# Frequency_synthesizer_v1_0.net
KiCad netlist of a schematic drawn in EAGLE
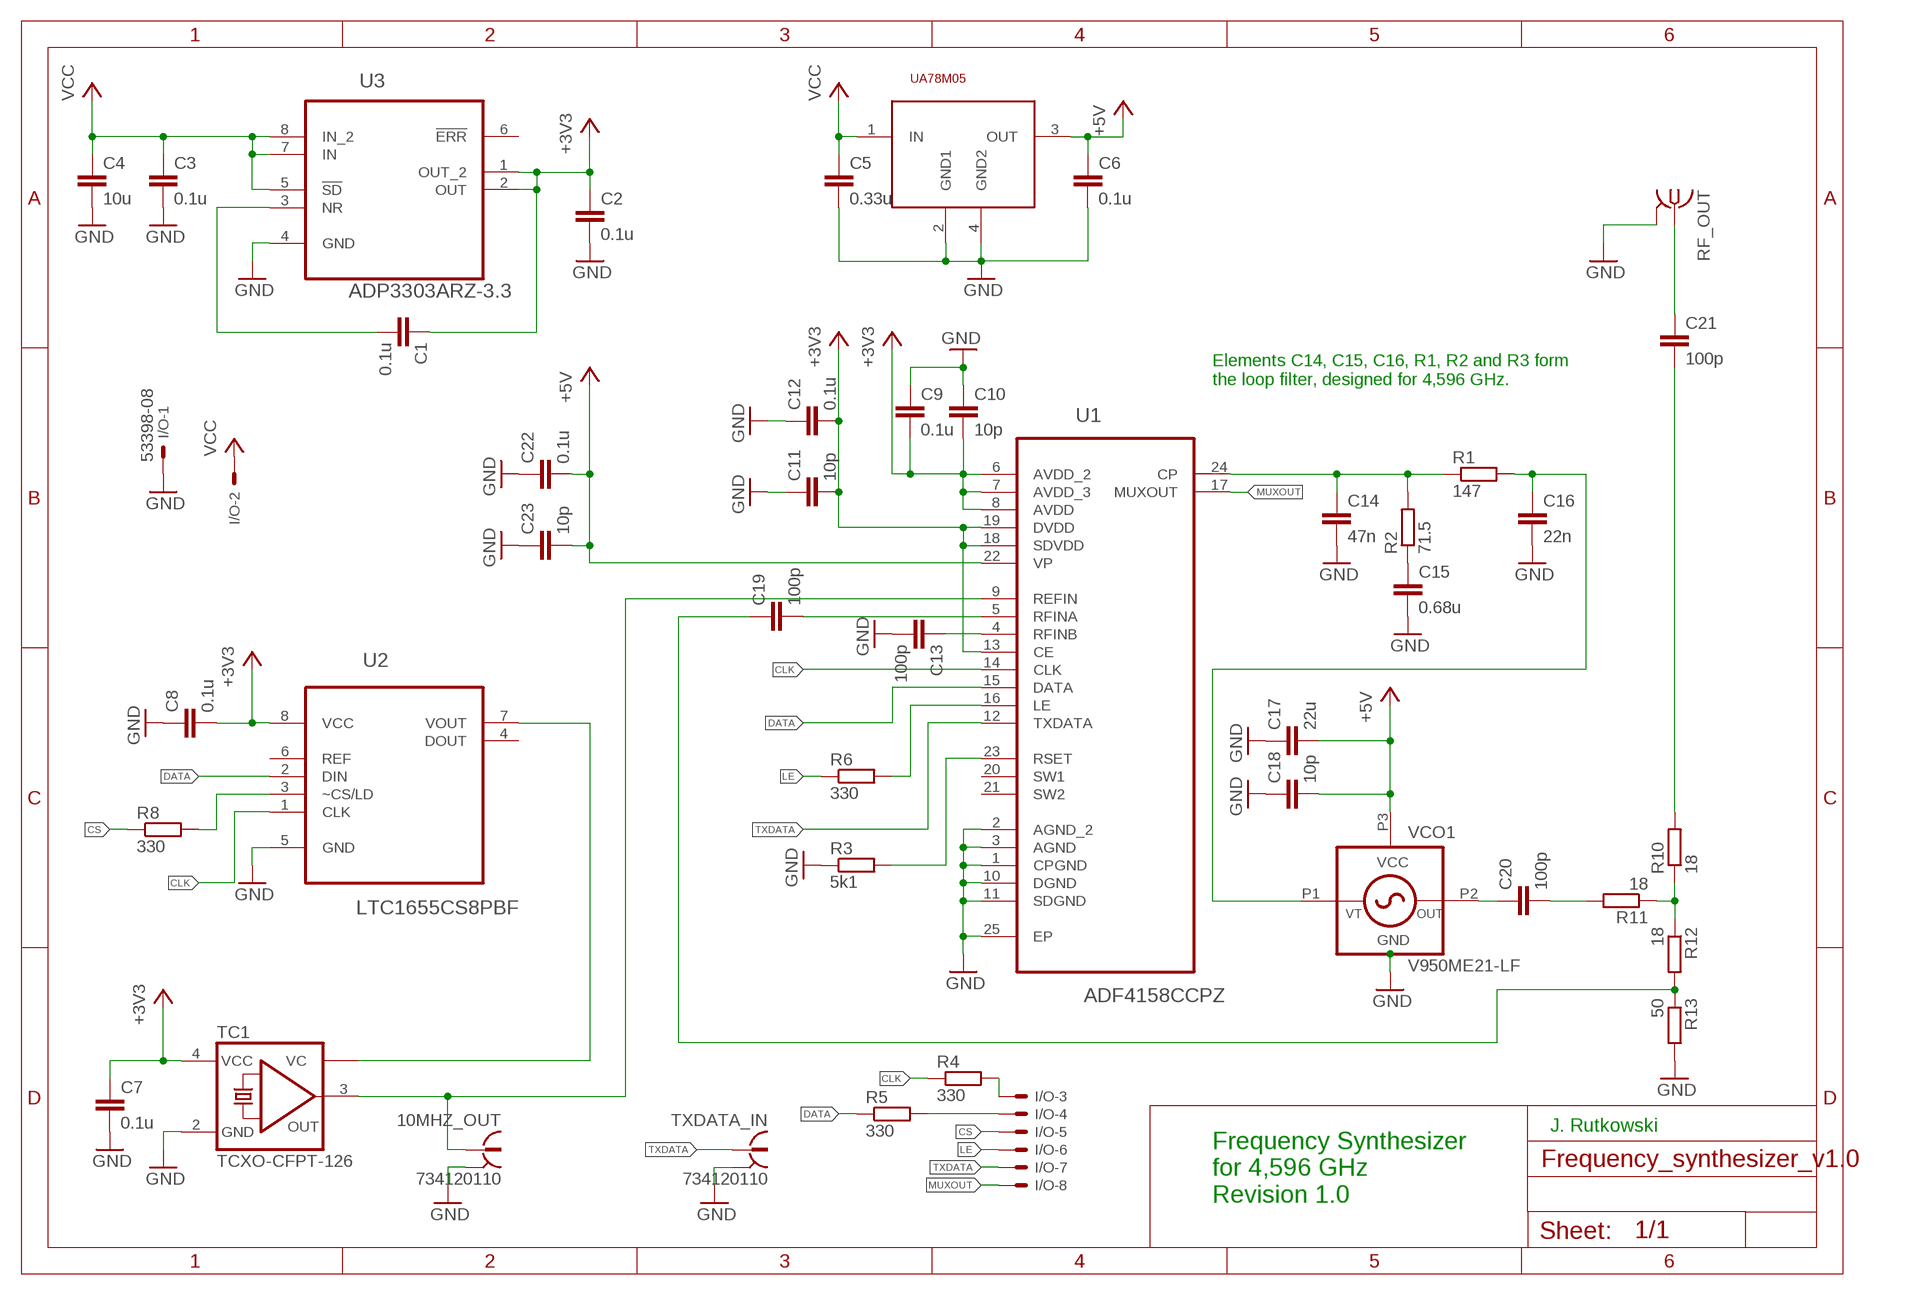
[diagram p0: schematic, sheet 1]

(export (version "E")
  (design (tool "Eeschema 10.0.6"))
  (components
    (comp (ref "10MHZ_OUT")
      (value "734120110")
      (footprint "eagle-import:734120110")
      (libsource (lib "eagle-import") (part "734120110"))
    )
    (comp (ref "C1")
      (value "0.1u")
      (footprint "eagle-import:C0603K")
      (libsource (lib "eagle-import") (part "C-EUC0603K"))
    )
    (comp (ref "C2")
      (value "0.1u")
      (footprint "eagle-import:C0603K")
      (libsource (lib "eagle-import") (part "C-EUC0603K"))
    )
    (comp (ref "C3")
      (value "0.1u")
      (footprint "eagle-import:C0603K")
      (libsource (lib "eagle-import") (part "C-EUC0603K"))
    )
    (comp (ref "C4")
      (value "10u")
      (footprint "eagle-import:C0805K")
      (libsource (lib "eagle-import") (part "C-EUC0805K"))
    )
    (comp (ref "C5")
      (value "0.33u")
      (footprint "eagle-import:C0603K")
      (libsource (lib "eagle-import") (part "C-EUC0603K"))
    )
    (comp (ref "C6")
      (value "0.1u")
      (footprint "eagle-import:C0603K")
      (libsource (lib "eagle-import") (part "C-EUC0603K"))
    )
    (comp (ref "C7")
      (value "0.1u")
      (footprint "eagle-import:C0603K")
      (libsource (lib "eagle-import") (part "C-EUC0603K"))
    )
    (comp (ref "C8")
      (value "0.1u")
      (footprint "eagle-import:C0603K")
      (libsource (lib "eagle-import") (part "C-EUC0603K"))
    )
    (comp (ref "C9")
      (value "0.1u")
      (footprint "eagle-import:C0603K")
      (libsource (lib "eagle-import") (part "C-EUC0603K"))
    )
    (comp (ref "C10")
      (value "10p")
      (footprint "eagle-import:C0603K")
      (libsource (lib "eagle-import") (part "C-EUC0603K"))
    )
    (comp (ref "C11")
      (value "10p")
      (footprint "eagle-import:C0603K")
      (libsource (lib "eagle-import") (part "C-EUC0603K"))
    )
    (comp (ref "C12")
      (value "0.1u")
      (footprint "eagle-import:C0603K")
      (libsource (lib "eagle-import") (part "C-EUC0603K"))
    )
    (comp (ref "C13")
      (value "100p")
      (footprint "eagle-import:C0402")
      (libsource (lib "eagle-import") (part "C-EUC0402"))
    )
    (comp (ref "C14")
      (value "47n")
      (footprint "eagle-import:C0603K")
      (libsource (lib "eagle-import") (part "C-EUC0603K"))
    )
    (comp (ref "C15")
      (value "0.68u")
      (footprint "eagle-import:C0603K")
      (libsource (lib "eagle-import") (part "C-EUC0603K"))
    )
    (comp (ref "C16")
      (value "22n")
      (footprint "eagle-import:C0603K")
      (libsource (lib "eagle-import") (part "C-EUC0603K"))
    )
    (comp (ref "C17")
      (value "22u")
      (footprint "eagle-import:C0805")
      (libsource (lib "eagle-import") (part "C-EUC0805"))
    )
    (comp (ref "C18")
      (value "10p")
      (footprint "eagle-import:C0603K")
      (libsource (lib "eagle-import") (part "C-EUC0603K"))
    )
    (comp (ref "C19")
      (value "100p")
      (footprint "eagle-import:C0402")
      (libsource (lib "eagle-import") (part "C-EUC0402"))
    )
    (comp (ref "C20")
      (value "100p")
      (footprint "eagle-import:C0402")
      (libsource (lib "eagle-import") (part "C-EUC0402"))
    )
    (comp (ref "C21")
      (value "100p")
      (footprint "eagle-import:C0402")
      (libsource (lib "eagle-import") (part "C-EUC0402"))
    )
    (comp (ref "C22")
      (value "0.1u")
      (footprint "eagle-import:C0603K")
      (libsource (lib "eagle-import") (part "C-EUC0603K"))
    )
    (comp (ref "C23")
      (value "10p")
      (footprint "eagle-import:C0603K")
      (libsource (lib "eagle-import") (part "C-EUC0603K"))
    )
    (comp (ref "I/O")
      (value "53398-08")
      (footprint "eagle-import:53398-08")
      (libsource (lib "eagle-import") (part "53?-08398"))
    )
    (comp (ref "R1")
      (value "147")
      (footprint "eagle-import:R0603")
      (libsource (lib "eagle-import") (part "R-EU_R0603"))
    )
    (comp (ref "R2")
      (value "71.5")
      (footprint "eagle-import:R0603")
      (libsource (lib "eagle-import") (part "R-EU_R0603"))
    )
    (comp (ref "R3")
      (value "5k1")
      (footprint "eagle-import:R0603")
      (libsource (lib "eagle-import") (part "R-EU_R0603"))
    )
    (comp (ref "R4")
      (value "330")
      (footprint "eagle-import:R0603")
      (libsource (lib "eagle-import") (part "R-EU_R0603"))
    )
    (comp (ref "R5")
      (value "330")
      (footprint "eagle-import:R0603")
      (libsource (lib "eagle-import") (part "R-EU_R0603"))
    )
    (comp (ref "R6")
      (value "330")
      (footprint "eagle-import:R0603")
      (libsource (lib "eagle-import") (part "R-EU_R0603"))
    )
    (comp (ref "R8")
      (value "330")
      (footprint "eagle-import:R0603")
      (libsource (lib "eagle-import") (part "R-EU_R0603"))
    )
    (comp (ref "R10")
      (value "18")
      (footprint "eagle-import:R0402")
      (libsource (lib "eagle-import") (part "R-EU_R0402"))
    )
    (comp (ref "R11")
      (value "18")
      (footprint "eagle-import:R0402")
      (libsource (lib "eagle-import") (part "R-EU_R0402"))
    )
    (comp (ref "R12")
      (value "18")
      (footprint "eagle-import:R0402")
      (libsource (lib "eagle-import") (part "R-EU_R0402"))
    )
    (comp (ref "R13")
      (value "50")
      (footprint "eagle-import:R0402")
      (libsource (lib "eagle-import") (part "R-EU_R0402"))
    )
    (comp (ref "RF_OUT")
      (value "SMA-142-0711-871/876")
      (footprint "eagle-import:J502-ND-142-0711-871_876")
      (fields (field (name "MF") "JOHNSON COMPONENTS") (field (name "MPN") "142-0711-871"))
      (libsource (lib "eagle-import") (part "SMA-142-0711-871/876"))
    )
    (comp (ref "TC1")
      (value "TCXO-CFPT-126")
      (footprint "eagle-import:7.0X5.0-4-PAD")
      (libsource (lib "eagle-import") (part "TCXO-CFPT-126"))
    )
    (comp (ref "TXDATA_IN")
      (value "734120110")
      (footprint "eagle-import:734120110")
      (libsource (lib "eagle-import") (part "734120110"))
    )
    (comp (ref "U$1")
      (value "UA78M05")
      (footprint "eagle-import:SOT-223")
      (libsource (lib "eagle-import") (part "UA78M05"))
    )
    (comp (ref "U1")
      (value "ADF4158CCPZ")
      (footprint "eagle-import:QFN50P400X400X80-25N")
      (libsource (lib "eagle-import") (part "ADF4158CCPZ"))
    )
    (comp (ref "U2")
      (value "LTC1655CS8PBF")
      (footprint "eagle-import:SOIC127P600X175-8N")
      (fields (field (name "MPN") "LTC1655CS8#PBF"))
      (libsource (lib "eagle-import") (part "LTC1655CS8PBF"))
    )
    (comp (ref "U3")
      (value "ADP3303ARZ-3.3")
      (footprint "eagle-import:SOIC127P600X175-8N")
      (libsource (lib "eagle-import") (part "ADP3303ARZ-3.3"))
    )
    (comp (ref "VCO1")
      (value "V950ME21-LF")
      (footprint "eagle-import:MINI-14S")
      (libsource (lib "eagle-import") (part "MINI-14S"))
    )
  )
  (nets
    (net (code "1") (name "+3V3") (class "Default")
      (node (ref "C1") (pin "1") (pinfunction "1_1") (pintype "passive"))
      (node (ref "C10") (pin "2") (pinfunction "2_2") (pintype "passive"))
      (node (ref "C11") (pin "2") (pinfunction "2_2") (pintype "passive"))
      (node (ref "C12") (pin "2") (pinfunction "2_2") (pintype "passive"))
      (node (ref "C2") (pin "1") (pinfunction "1_1") (pintype "passive"))
      (node (ref "C7") (pin "1") (pinfunction "1_1") (pintype "passive"))
      (node (ref "C8") (pin "2") (pinfunction "2_2") (pintype "passive"))
      (node (ref "C9") (pin "2") (pinfunction "2_2") (pintype "passive"))
      (node (ref "TC1") (pin "4") (pinfunction "VCC_4") (pintype "power_in"))
      (node (ref "U1") (pin "13") (pinfunction "CE_13") (pintype "input"))
      (node (ref "U1") (pin "18") (pinfunction "SDVDD_18") (pintype "power_in"))
      (node (ref "U1") (pin "19") (pinfunction "DVDD_19") (pintype "power_in"))
      (node (ref "U1") (pin "6") (pinfunction "AVDD_2_6") (pintype "power_in"))
      (node (ref "U1") (pin "7") (pinfunction "AVDD_3_7") (pintype "power_in"))
      (node (ref "U1") (pin "8") (pinfunction "AVDD_8") (pintype "power_in"))
      (node (ref "U2") (pin "8") (pinfunction "VCC_8") (pintype "power_in"))
      (node (ref "U3") (pin "1") (pinfunction "OUT_2_1") (pintype "output"))
      (node (ref "U3") (pin "2") (pinfunction "OUT_2") (pintype "output"))
    )
    (net (code "2") (name "+5V") (class "Default")
      (node (ref "C17") (pin "2") (pinfunction "2_2") (pintype "passive"))
      (node (ref "C18") (pin "2") (pinfunction "2_2") (pintype "passive"))
      (node (ref "C22") (pin "2") (pinfunction "2_2") (pintype "passive"))
      (node (ref "C23") (pin "2") (pinfunction "2_2") (pintype "passive"))
      (node (ref "C6") (pin "1") (pinfunction "1_1") (pintype "passive"))
      (node (ref "U$1") (pin "3") (pinfunction "OUT_3") (pintype "bidirectional"))
      (node (ref "U1") (pin "22") (pinfunction "VP_22") (pintype "power_in"))
      (node (ref "VCO1") (pin "P3") (pinfunction "VCC_P3") (pintype "power_in"))
    )
    (net (code "3") (name "CLK") (class "Default")
      (node (ref "R4") (pin "1") (pinfunction "1_1") (pintype "passive"))
      (node (ref "U1") (pin "14") (pinfunction "CLK_14") (pintype "input"))
      (node (ref "U2") (pin "1") (pinfunction "CLK_1") (pintype "input"))
    )
    (net (code "4") (name "CS") (class "Default")
      (node (ref "I/O") (pin "5") (pinfunction "S_5") (pintype "passive"))
      (node (ref "R8") (pin "1") (pinfunction "1_1") (pintype "passive"))
    )
    (net (code "5") (name "DATA") (class "Default")
      (node (ref "R5") (pin "1") (pinfunction "1_1") (pintype "passive"))
      (node (ref "U1") (pin "15") (pinfunction "DATA_15") (pintype "input"))
      (node (ref "U2") (pin "2") (pinfunction "DIN_2") (pintype "input"))
    )
    (net (code "6") (name "GND") (class "Default")
      (node (ref "10MHZ_OUT") (pin "S@1") (pinfunction "2_S@1") (pintype "passive"))
      (node (ref "10MHZ_OUT") (pin "S@2") (pinfunction "2_S@2") (pintype "passive"))
      (node (ref "10MHZ_OUT") (pin "S@3") (pinfunction "2_S@3") (pintype "passive"))
      (node (ref "C10") (pin "1") (pinfunction "1_1") (pintype "passive"))
      (node (ref "C11") (pin "1") (pinfunction "1_1") (pintype "passive"))
      (node (ref "C12") (pin "1") (pinfunction "1_1") (pintype "passive"))
      (node (ref "C13") (pin "2") (pinfunction "2_2") (pintype "passive"))
      (node (ref "C14") (pin "2") (pinfunction "2_2") (pintype "passive"))
      (node (ref "C15") (pin "2") (pinfunction "2_2") (pintype "passive"))
      (node (ref "C16") (pin "2") (pinfunction "2_2") (pintype "passive"))
      (node (ref "C17") (pin "1") (pinfunction "1_1") (pintype "passive"))
      (node (ref "C18") (pin "1") (pinfunction "1_1") (pintype "passive"))
      (node (ref "C2") (pin "2") (pinfunction "2_2") (pintype "passive"))
      (node (ref "C22") (pin "1") (pinfunction "1_1") (pintype "passive"))
      (node (ref "C23") (pin "1") (pinfunction "1_1") (pintype "passive"))
      (node (ref "C3") (pin "2") (pinfunction "2_2") (pintype "passive"))
      (node (ref "C4") (pin "2") (pinfunction "2_2") (pintype "passive"))
      (node (ref "C5") (pin "2") (pinfunction "2_2") (pintype "passive"))
      (node (ref "C6") (pin "2") (pinfunction "2_2") (pintype "passive"))
      (node (ref "C7") (pin "2") (pinfunction "2_2") (pintype "passive"))
      (node (ref "C8") (pin "1") (pinfunction "1_1") (pintype "passive"))
      (node (ref "C9") (pin "1") (pinfunction "1_1") (pintype "passive"))
      (node (ref "I/O") (pin "1") (pinfunction "S_1") (pintype "passive"))
      (node (ref "R13") (pin "2") (pinfunction "2_2") (pintype "passive"))
      (node (ref "R3") (pin "1") (pinfunction "1_1") (pintype "passive"))
      (node (ref "RF_OUT") (pin "G@1") (pinfunction "2_G@1") (pintype "passive"))
      (node (ref "RF_OUT") (pin "G@2") (pinfunction "2_G@2") (pintype "passive"))
      (node (ref "RF_OUT") (pin "G@3") (pinfunction "2_G@3") (pintype "passive"))
      (node (ref "RF_OUT") (pin "G@4") (pinfunction "2_G@4") (pintype "passive"))
      (node (ref "TC1") (pin "2") (pinfunction "GND_2") (pintype "power_in"))
      (node (ref "TXDATA_IN") (pin "S@1") (pinfunction "2_S@1") (pintype "passive"))
      (node (ref "TXDATA_IN") (pin "S@2") (pinfunction "2_S@2") (pintype "passive"))
      (node (ref "TXDATA_IN") (pin "S@3") (pinfunction "2_S@3") (pintype "passive"))
      (node (ref "U$1") (pin "2") (pinfunction "GND1_2") (pintype "bidirectional"))
      (node (ref "U$1") (pin "4") (pinfunction "GND2_4") (pintype "bidirectional"))
      (node (ref "U1") (pin "1") (pinfunction "CPGND_1") (pintype "passive"))
      (node (ref "U1") (pin "10") (pinfunction "DGND_10") (pintype "passive"))
      (node (ref "U1") (pin "11") (pinfunction "SDGND_11") (pintype "passive"))
      (node (ref "U1") (pin "2") (pinfunction "AGND_2_2") (pintype "passive"))
      (node (ref "U1") (pin "25") (pinfunction "EP_25") (pintype "passive"))
      (node (ref "U1") (pin "3") (pinfunction "AGND_3") (pintype "passive"))
      (node (ref "U2") (pin "5") (pinfunction "GND_5") (pintype "passive"))
      (node (ref "U3") (pin "4") (pinfunction "GND_4") (pintype "passive"))
      (node (ref "VCO1") (pin "S1") (pinfunction "S1_S1") (pintype "power_in"))
      (node (ref "VCO1") (pin "S10") (pinfunction "S10_S10") (pintype "power_in"))
      (node (ref "VCO1") (pin "S11") (pinfunction "S11_S11") (pintype "power_in"))
      (node (ref "VCO1") (pin "S2") (pinfunction "S2_S2") (pintype "power_in"))
      (node (ref "VCO1") (pin "S3") (pinfunction "S3_S3") (pintype "power_in"))
      (node (ref "VCO1") (pin "S4") (pinfunction "S4_S4") (pintype "power_in"))
      (node (ref "VCO1") (pin "S5") (pinfunction "S5_S5") (pintype "power_in"))
      (node (ref "VCO1") (pin "S6") (pinfunction "S6_S6") (pintype "power_in"))
      (node (ref "VCO1") (pin "S7") (pinfunction "S7_S7") (pintype "power_in"))
      (node (ref "VCO1") (pin "S8") (pinfunction "S8_S8") (pintype "power_in"))
      (node (ref "VCO1") (pin "S9") (pinfunction "S9_S9") (pintype "power_in"))
    )
    (net (code "7") (name "LE") (class "Default")
      (node (ref "I/O") (pin "6") (pinfunction "S_6") (pintype "passive"))
      (node (ref "R6") (pin "1") (pinfunction "1_1") (pintype "passive"))
    )
    (net (code "8") (name "MUXOUT") (class "Default")
      (node (ref "I/O") (pin "8") (pinfunction "S_8") (pintype "passive"))
      (node (ref "U1") (pin "17") (pinfunction "MUXOUT_17") (pintype "output"))
    )
    (net (code "9") (name "Net-(C15-Pad1)") (class "Default")
      (node (ref "C15") (pin "1") (pinfunction "1_1") (pintype "passive"))
      (node (ref "R2") (pin "1") (pinfunction "1_1") (pintype "passive"))
    )
    (net (code "10") (name "Net-(C19-Pad1)") (class "Default")
      (node (ref "C19") (pin "1") (pinfunction "1_1") (pintype "passive"))
      (node (ref "R12") (pin "2") (pinfunction "2_2") (pintype "passive"))
      (node (ref "R13") (pin "1") (pinfunction "1_1") (pintype "passive"))
    )
    (net (code "11") (name "Net-(C20-Pad2)") (class "Default")
      (node (ref "C20") (pin "2") (pinfunction "2_2") (pintype "passive"))
      (node (ref "R11") (pin "2") (pinfunction "2_2") (pintype "passive"))
    )
    (net (code "12") (name "Net-(C21-Pad1)") (class "Default")
      (node (ref "C21") (pin "1") (pinfunction "1_1") (pintype "passive"))
      (node (ref "RF_OUT") (pin "1") (pinfunction "1_1") (pintype "passive"))
    )
    (net (code "13") (name "Net-(C21-Pad2)") (class "Default")
      (node (ref "C21") (pin "2") (pinfunction "2_2") (pintype "passive"))
      (node (ref "R10") (pin "2") (pinfunction "2_2") (pintype "passive"))
    )
    (net (code "14") (name "Net-(I/OC-S)") (class "Default")
      (node (ref "I/O") (pin "3") (pinfunction "S_3") (pintype "passive"))
      (node (ref "R4") (pin "2") (pinfunction "2_2") (pintype "passive"))
    )
    (net (code "15") (name "Net-(I/OD-S)") (class "Default")
      (node (ref "I/O") (pin "4") (pinfunction "S_4") (pintype "passive"))
      (node (ref "R5") (pin "2") (pinfunction "2_2") (pintype "passive"))
    )
    (net (code "16") (name "Net-(R10-Pad1)") (class "Default")
      (node (ref "R10") (pin "1") (pinfunction "1_1") (pintype "passive"))
      (node (ref "R11") (pin "1") (pinfunction "1_1") (pintype "passive"))
      (node (ref "R12") (pin "1") (pinfunction "1_1") (pintype "passive"))
    )
    (net (code "17") (name "Net-(TC1-OUT)") (class "Default")
      (node (ref "10MHZ_OUT") (pin "1") (pinfunction "1_1") (pintype "passive"))
      (node (ref "TC1") (pin "3") (pinfunction "OUT_3") (pintype "output"))
      (node (ref "U1") (pin "9") (pinfunction "REFIN_9") (pintype "input"))
    )
    (net (code "18") (name "Net-(TC1-VC)") (class "Default")
      (node (ref "TC1") (pin "1") (pinfunction "VC_1") (pintype "input"))
      (node (ref "U2") (pin "7") (pinfunction "VOUT_7") (pintype "output"))
    )
    (net (code "19") (name "Net-(U1-CP)") (class "Default")
      (node (ref "C14") (pin "1") (pinfunction "1_1") (pintype "passive"))
      (node (ref "R1") (pin "1") (pinfunction "1_1") (pintype "passive"))
      (node (ref "R2") (pin "2") (pinfunction "2_2") (pintype "passive"))
      (node (ref "U1") (pin "24") (pinfunction "CP_24") (pintype "output"))
    )
    (net (code "20") (name "Net-(U1-LE)") (class "Default")
      (node (ref "R6") (pin "2") (pinfunction "2_2") (pintype "passive"))
      (node (ref "U1") (pin "16") (pinfunction "LE_16") (pintype "input"))
    )
    (net (code "21") (name "Net-(U1-RFINA)") (class "Default")
      (node (ref "C19") (pin "2") (pinfunction "2_2") (pintype "passive"))
      (node (ref "U1") (pin "5") (pinfunction "RFINA_5") (pintype "input"))
    )
    (net (code "22") (name "Net-(U1-RFINB)") (class "Default")
      (node (ref "C13") (pin "1") (pinfunction "1_1") (pintype "passive"))
      (node (ref "U1") (pin "4") (pinfunction "RFINB_4") (pintype "input"))
    )
    (net (code "23") (name "Net-(U1-RSET)") (class "Default")
      (node (ref "R3") (pin "2") (pinfunction "2_2") (pintype "passive"))
      (node (ref "U1") (pin "23") (pinfunction "RSET_23") (pintype "passive"))
    )
    (net (code "24") (name "Net-(U2-~{CS{slash}LD})") (class "Default")
      (node (ref "R8") (pin "2") (pinfunction "2_2") (pintype "passive"))
      (node (ref "U2") (pin "3") (pinfunction "~{CS/LD}_3") (pintype "input"))
    )
    (net (code "25") (name "Net-(U3-NR)") (class "Default")
      (node (ref "C1") (pin "2") (pinfunction "2_2") (pintype "passive"))
      (node (ref "U3") (pin "3") (pinfunction "NR_3") (pintype "input"))
    )
    (net (code "26") (name "Net-(VCO1-OUT)") (class "Default")
      (node (ref "C20") (pin "1") (pinfunction "1_1") (pintype "passive"))
      (node (ref "VCO1") (pin "P2") (pinfunction "OUT_P2") (pintype "output"))
    )
    (net (code "27") (name "Net-(VCO1-VT)") (class "Default")
      (node (ref "C16") (pin "1") (pinfunction "1_1") (pintype "passive"))
      (node (ref "R1") (pin "2") (pinfunction "2_2") (pintype "passive"))
      (node (ref "VCO1") (pin "P1") (pinfunction "VT_P1") (pintype "input"))
    )
    (net (code "28") (name "TXDATA") (class "Default")
      (node (ref "I/O") (pin "7") (pinfunction "S_7") (pintype "passive"))
      (node (ref "TXDATA_IN") (pin "1") (pinfunction "1_1") (pintype "passive"))
      (node (ref "U1") (pin "12") (pinfunction "TXDATA_12") (pintype "input"))
    )
    (net (code "29") (name "VCC") (class "Default")
      (node (ref "C3") (pin "1") (pinfunction "1_1") (pintype "passive"))
      (node (ref "C4") (pin "1") (pinfunction "1_1") (pintype "passive"))
      (node (ref "C5") (pin "1") (pinfunction "1_1") (pintype "passive"))
      (node (ref "I/O") (pin "2") (pinfunction "S_2") (pintype "passive"))
      (node (ref "U$1") (pin "1") (pinfunction "IN_1") (pintype "bidirectional"))
      (node (ref "U3") (pin "5") (pinfunction "~{SD}_5") (pintype "input"))
      (node (ref "U3") (pin "7") (pinfunction "IN_7") (pintype "input"))
      (node (ref "U3") (pin "8") (pinfunction "IN_2_8") (pintype "input"))
    )
    (net (code "30") (name "unconnected-(U1-SW1-Pad20)") (class "Default")
      (node (ref "U1") (pin "20") (pinfunction "SW1_20") (pintype "passive"))
    )
    (net (code "31") (name "unconnected-(U1-SW2-Pad21)") (class "Default")
      (node (ref "U1") (pin "21") (pinfunction "SW2_21") (pintype "passive"))
    )
    (net (code "32") (name "unconnected-(U2-DOUT-Pad4)") (class "Default")
      (node (ref "U2") (pin "4") (pinfunction "DOUT_4") (pintype "output"))
    )
    (net (code "33") (name "unconnected-(U2-REF-Pad6)") (class "Default")
      (node (ref "U2") (pin "6") (pinfunction "REF_6") (pintype "input"))
    )
    (net (code "34") (name "unconnected-(U3-~{ERR}-Pad6)") (class "Default")
      (node (ref "U3") (pin "6") (pinfunction "~{ERR}_6") (pintype "output"))
    )
  )
)
